# working.net
KiCad netlist of a schematic drawn in EAGLE
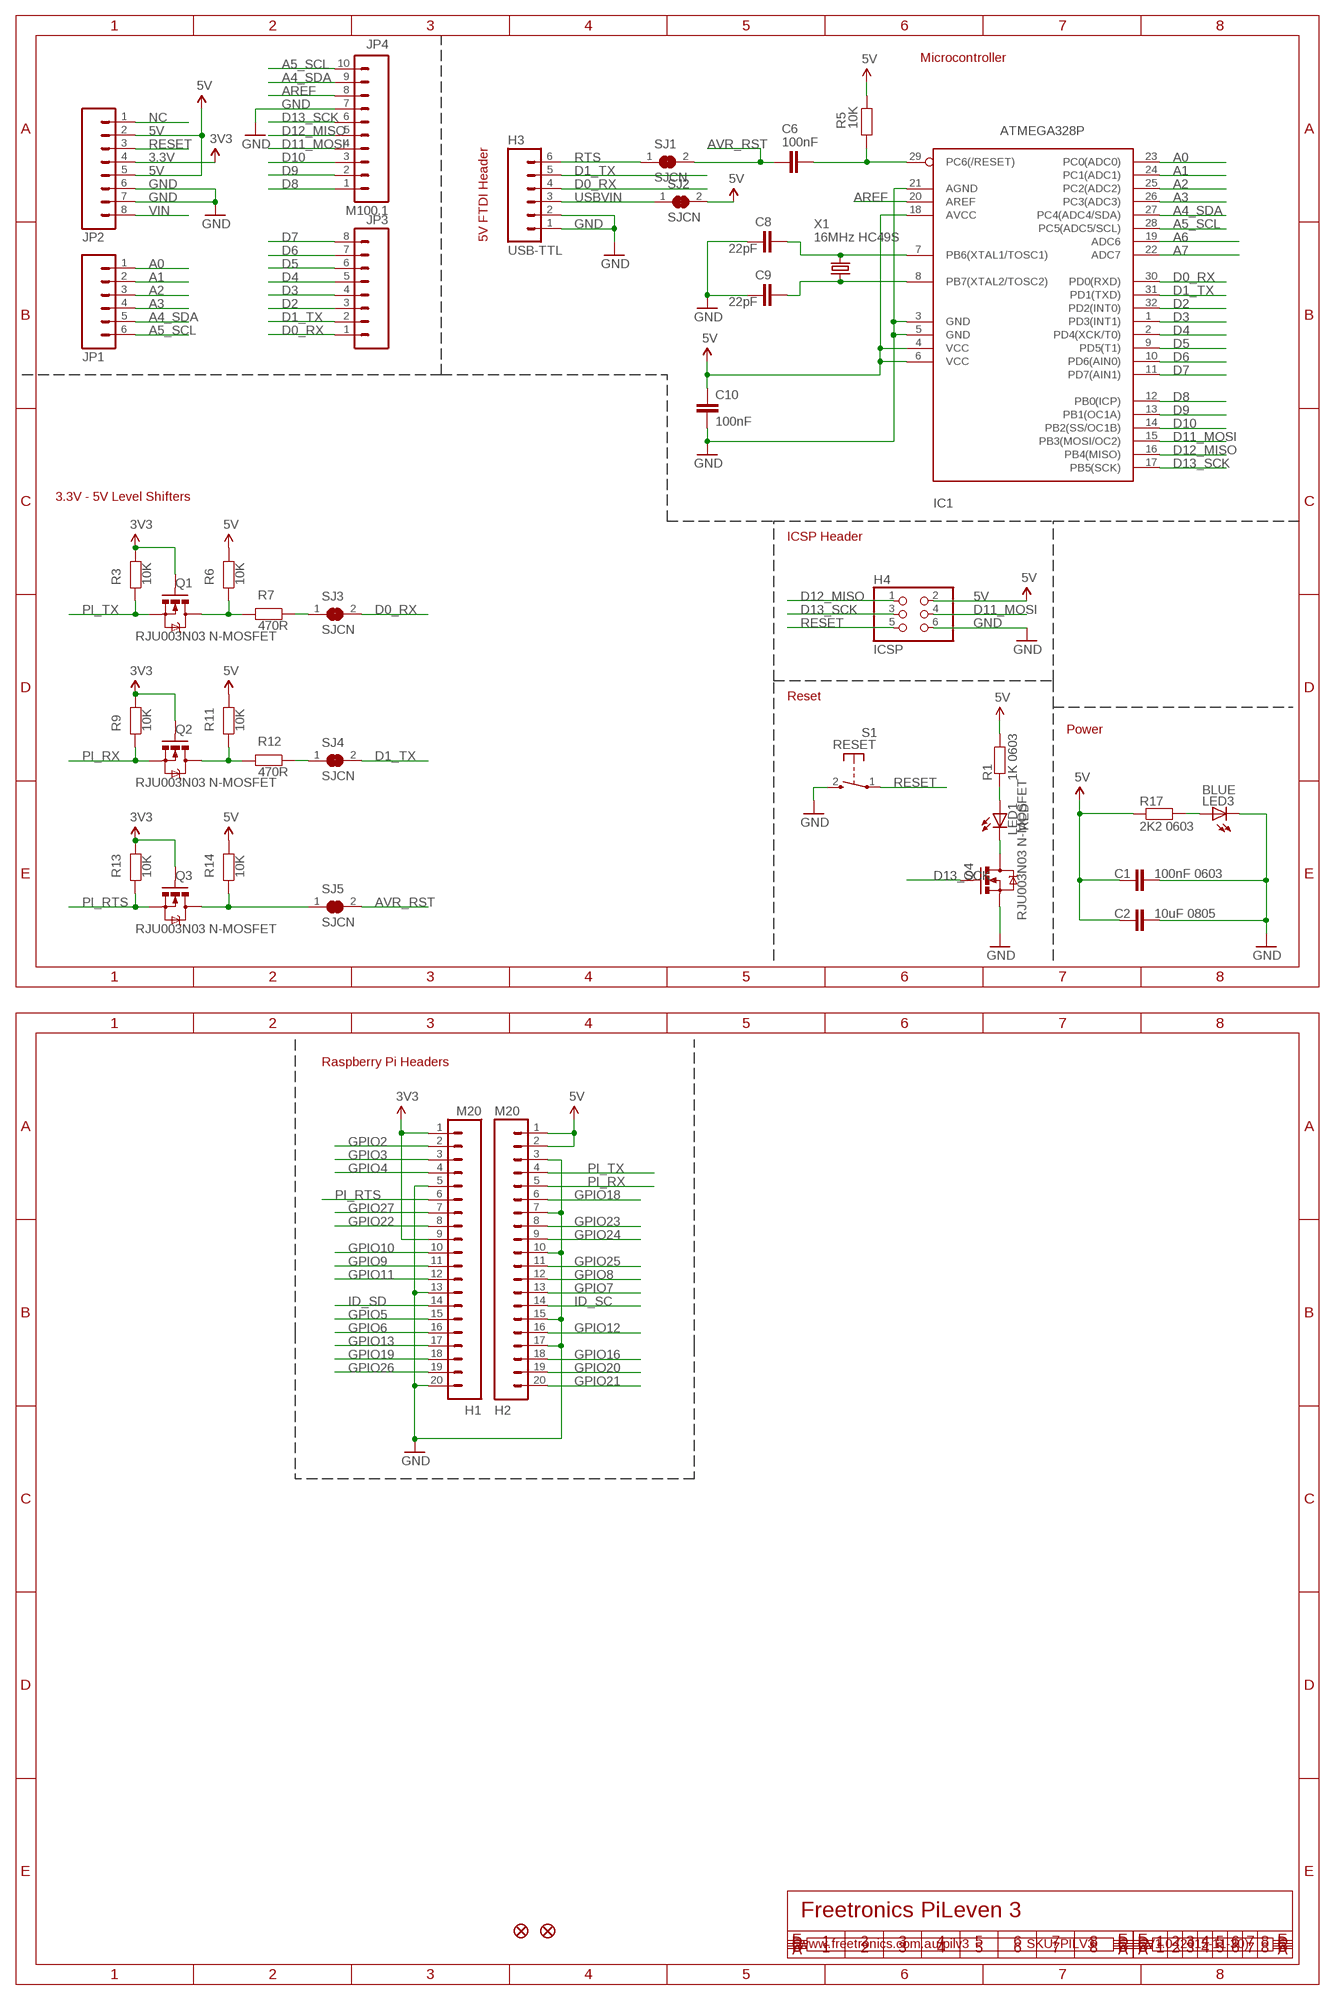
[diagram p0: schematic, sheet 1]

(export (version "E")
  (design (tool "Eeschema 10.0.6"))
  (components
    (comp (ref "C1")
      (value "100nF 0603")
      (footprint "eagle-import:0603")
      (libsource (lib "eagle-import") (part "CAP0603"))
    )
    (comp (ref "C2")
      (value "10uF 0805")
      (footprint "eagle-import:C0805")
      (libsource (lib "eagle-import") (part "C-EUC0805"))
    )
    (comp (ref "C6")
      (value "100nF")
      (footprint "eagle-import:0603")
      (libsource (lib "eagle-import") (part "freetronics-master-v1.1_CAP0603"))
    )
    (comp (ref "C8")
      (value "22pF")
      (footprint "eagle-import:0603")
      (libsource (lib "eagle-import") (part "freetronics-master-v1.1_CAP0603"))
    )
    (comp (ref "C9")
      (value "22pF")
      (footprint "eagle-import:0603")
      (libsource (lib "eagle-import") (part "freetronics-master-v1.1_CAP0603"))
    )
    (comp (ref "C10")
      (value "100nF")
      (footprint "eagle-import:0603")
      (libsource (lib "eagle-import") (part "freetronics-master-v1.1_CAP0603"))
    )
    (comp (ref "H1")
      (value "M20")
      (footprint "eagle-import:1X20")
      (libsource (lib "eagle-import") (part "M20"))
    )
    (comp (ref "H2")
      (value "M20")
      (footprint "eagle-import:1X20")
      (libsource (lib "eagle-import") (part "M20"))
    )
    (comp (ref "H3")
      (value "USB-TTL")
      (footprint "eagle-import:1X06")
      (libsource (lib "eagle-import") (part "M06SIP"))
    )
    (comp (ref "H4")
      (value "ICSP")
      (footprint "eagle-import:2X03")
      (libsource (lib "eagle-import") (part "PINHD-2X3"))
    )
    (comp (ref "IC1")
      (value "ATMEGA328P")
      (footprint "eagle-import:TQFP32-08")
      (libsource (lib "eagle-import") (part "AVR-MEGA8-AI"))
    )
    (comp (ref "JP1")
      (value "M06SIP")
      (footprint "eagle-import:1X06")
      (libsource (lib "eagle-import") (part "freetronics-original_M06SIP"))
    )
    (comp (ref "JP2")
      (value "M08")
      (footprint "eagle-import:1X08")
      (libsource (lib "eagle-import") (part "M08"))
    )
    (comp (ref "JP3")
      (value "M08")
      (footprint "eagle-import:1X08")
      (libsource (lib "eagle-import") (part "M08"))
    )
    (comp (ref "JP4")
      (value "M100.1")
      (footprint "eagle-import:1X10")
      (libsource (lib "eagle-import") (part "M100.1"))
    )
    (comp (ref "LED1")
      (value "RED")
      (footprint "eagle-import:LED-0603")
      (libsource (lib "eagle-import") (part "LED0603"))
    )
    (comp (ref "LED3")
      (value "BLUE")
      (footprint "eagle-import:LED-0603")
      (libsource (lib "eagle-import") (part "LED0603"))
    )
    (comp (ref "Q1")
      (value "RJU003N03 N-MOSFET")
      (footprint "eagle-import:SOT32-3")
      (libsource (lib "eagle-import") (part "MOSFET-NSOT-323"))
    )
    (comp (ref "Q2")
      (value "RJU003N03 N-MOSFET")
      (footprint "eagle-import:SOT32-3")
      (libsource (lib "eagle-import") (part "MOSFET-NSOT-323"))
    )
    (comp (ref "Q3")
      (value "RJU003N03 N-MOSFET")
      (footprint "eagle-import:SOT32-3")
      (libsource (lib "eagle-import") (part "MOSFET-NSOT-323"))
    )
    (comp (ref "Q4")
      (value "RJU003N03 N-MOSFET")
      (footprint "eagle-import:SOT32-3")
      (libsource (lib "eagle-import") (part "MOSFET-NSOT-323"))
    )
    (comp (ref "R1")
      (value "1K 0603")
      (footprint "eagle-import:0603")
      (libsource (lib "eagle-import") (part "RESISTOR0603"))
    )
    (comp (ref "R3")
      (value "10K")
      (footprint "eagle-import:0603")
      (libsource (lib "eagle-import") (part "freetronics-master-v1.1_RESISTOR0603"))
    )
    (comp (ref "R5")
      (value "10K")
      (footprint "eagle-import:0603")
      (libsource (lib "eagle-import") (part "freetronics-master-v1.1_RESISTOR0603"))
    )
    (comp (ref "R6")
      (value "10K")
      (footprint "eagle-import:0603")
      (libsource (lib "eagle-import") (part "freetronics-master-v1.1_RESISTOR0603"))
    )
    (comp (ref "R7")
      (value "470R")
      (footprint "eagle-import:0603")
      (libsource (lib "eagle-import") (part "freetronics-master-v1.1_RESISTOR0603"))
    )
    (comp (ref "R9")
      (value "10K")
      (footprint "eagle-import:0603")
      (libsource (lib "eagle-import") (part "freetronics-master-v1.1_RESISTOR0603"))
    )
    (comp (ref "R11")
      (value "10K")
      (footprint "eagle-import:0603")
      (libsource (lib "eagle-import") (part "freetronics-master-v1.1_RESISTOR0603"))
    )
    (comp (ref "R12")
      (value "470R")
      (footprint "eagle-import:0603")
      (libsource (lib "eagle-import") (part "freetronics-master-v1.1_RESISTOR0603"))
    )
    (comp (ref "R13")
      (value "10K")
      (footprint "eagle-import:0603")
      (libsource (lib "eagle-import") (part "freetronics-master-v1.1_RESISTOR0603"))
    )
    (comp (ref "R14")
      (value "10K")
      (footprint "eagle-import:0603")
      (libsource (lib "eagle-import") (part "freetronics-master-v1.1_RESISTOR0603"))
    )
    (comp (ref "R17")
      (value "2K2 0603")
      (footprint "eagle-import:0603")
      (libsource (lib "eagle-import") (part "RESISTOR0603"))
    )
    (comp (ref "S1")
      (value "RESET")
      (footprint "eagle-import:TACTILE_SWITCH_SMD_2PIN_TINY")
      (libsource (lib "eagle-import") (part "TAC_SWITCH_2PIN"))
    )
    (comp (ref "SJ1")
      (value "SJCN")
      (footprint "eagle-import:SJC")
      (libsource (lib "eagle-import") (part "SJCN"))
    )
    (comp (ref "SJ2")
      (value "SJCN")
      (footprint "eagle-import:SJC")
      (libsource (lib "eagle-import") (part "SJCN"))
    )
    (comp (ref "SJ3")
      (value "SJCN")
      (footprint "eagle-import:SJC")
      (libsource (lib "eagle-import") (part "SJCN"))
    )
    (comp (ref "SJ4")
      (value "SJCN")
      (footprint "eagle-import:SJC")
      (libsource (lib "eagle-import") (part "SJCN"))
    )
    (comp (ref "SJ5")
      (value "SJCN")
      (footprint "eagle-import:SJC")
      (libsource (lib "eagle-import") (part "SJCN"))
    )
    (comp (ref "U$4")
      (value "FIDUCIAL1X2.5")
      (footprint "eagle-import:FIDUCIAL-1X2.5")
      (libsource (lib "eagle-import") (part "FIDUCIAL1X2.5"))
    )
    (comp (ref "U$5")
      (value "FIDUCIAL1X2.5")
      (footprint "eagle-import:FIDUCIAL-1X2.5")
      (libsource (lib "eagle-import") (part "FIDUCIAL1X2.5"))
    )
    (comp (ref "X1")
      (value "16MHz HC49S")
      (footprint "eagle-import:HC49U-V")
      (libsource (lib "eagle-import") (part "CRYSTALHC49UV"))
    )
  )
  (nets
    (net (code "1") (name "/A0") (class "Default")
      (node (ref "IC1") (pin "23") (pinfunction "PC0(ADC0)_23") (pintype "bidirectional"))
      (node (ref "JP1") (pin "1") (pinfunction "1_1") (pintype "passive"))
    )
    (net (code "2") (name "/A1") (class "Default")
      (node (ref "IC1") (pin "24") (pinfunction "PC1(ADC1)_24") (pintype "bidirectional"))
      (node (ref "JP1") (pin "2") (pinfunction "2_2") (pintype "passive"))
    )
    (net (code "3") (name "/A2") (class "Default")
      (node (ref "IC1") (pin "25") (pinfunction "PC2(ADC2)_25") (pintype "bidirectional"))
      (node (ref "JP1") (pin "3") (pinfunction "3_3") (pintype "passive"))
    )
    (net (code "4") (name "/A3") (class "Default")
      (node (ref "IC1") (pin "26") (pinfunction "PC3(ADC3)_26") (pintype "bidirectional"))
      (node (ref "JP1") (pin "4") (pinfunction "4_4") (pintype "passive"))
    )
    (net (code "5") (name "/A4_SDA") (class "Default")
      (node (ref "IC1") (pin "27") (pinfunction "PC4(ADC4/SDA)_27") (pintype "bidirectional"))
      (node (ref "JP1") (pin "5") (pinfunction "5_5") (pintype "passive"))
      (node (ref "JP4") (pin "9") (pinfunction "9_9") (pintype "passive"))
    )
    (net (code "6") (name "/A5_SCL") (class "Default")
      (node (ref "IC1") (pin "28") (pinfunction "PC5(ADC5/SCL)_28") (pintype "bidirectional"))
      (node (ref "JP1") (pin "6") (pinfunction "6_6") (pintype "passive"))
      (node (ref "JP4") (pin "10") (pinfunction "10_10") (pintype "passive"))
    )
    (net (code "7") (name "/A6") (class "Default")
      (node (ref "IC1") (pin "19") (pinfunction "ADC6_19") (pintype "bidirectional"))
    )
    (net (code "8") (name "/A7") (class "Default")
      (node (ref "IC1") (pin "22") (pinfunction "ADC7_22") (pintype "bidirectional"))
    )
    (net (code "9") (name "/AREF") (class "Default")
      (node (ref "IC1") (pin "20") (pinfunction "AREF_20") (pintype "bidirectional"))
      (node (ref "JP4") (pin "8") (pinfunction "8_8") (pintype "passive"))
    )
    (net (code "10") (name "/AVR_RST") (class "Default")
      (node (ref "C6") (pin "1") (pinfunction "1_1") (pintype "passive"))
      (node (ref "SJ1") (pin "2") (pinfunction "2_2") (pintype "passive"))
      (node (ref "SJ5") (pin "2") (pinfunction "2_2") (pintype "passive"))
    )
    (net (code "11") (name "/D0_RX") (class "Default")
      (node (ref "H3") (pin "4") (pinfunction "4_4") (pintype "passive"))
      (node (ref "IC1") (pin "30") (pinfunction "PD0(RXD)_30") (pintype "bidirectional"))
      (node (ref "JP3") (pin "1") (pinfunction "1_1") (pintype "passive"))
      (node (ref "SJ3") (pin "2") (pinfunction "2_2") (pintype "passive"))
    )
    (net (code "12") (name "/D1_TX") (class "Default")
      (node (ref "H3") (pin "5") (pinfunction "5_5") (pintype "passive"))
      (node (ref "IC1") (pin "31") (pinfunction "PD1(TXD)_31") (pintype "bidirectional"))
      (node (ref "JP3") (pin "2") (pinfunction "2_2") (pintype "passive"))
      (node (ref "SJ4") (pin "2") (pinfunction "2_2") (pintype "passive"))
    )
    (net (code "13") (name "/D2") (class "Default")
      (node (ref "IC1") (pin "32") (pinfunction "PD2(INT0)_32") (pintype "bidirectional"))
      (node (ref "JP3") (pin "3") (pinfunction "3_3") (pintype "passive"))
    )
    (net (code "14") (name "/D3") (class "Default")
      (node (ref "IC1") (pin "1") (pinfunction "PD3(INT1)_1") (pintype "bidirectional"))
      (node (ref "JP3") (pin "4") (pinfunction "4_4") (pintype "passive"))
    )
    (net (code "15") (name "/D4") (class "Default")
      (node (ref "IC1") (pin "2") (pinfunction "PD4(XCK/T0)_2") (pintype "bidirectional"))
      (node (ref "JP3") (pin "5") (pinfunction "5_5") (pintype "passive"))
    )
    (net (code "16") (name "/D5") (class "Default")
      (node (ref "IC1") (pin "9") (pinfunction "PD5(T1)_9") (pintype "bidirectional"))
      (node (ref "JP3") (pin "6") (pinfunction "6_6") (pintype "passive"))
    )
    (net (code "17") (name "/D6") (class "Default")
      (node (ref "IC1") (pin "10") (pinfunction "PD6(AIN0)_10") (pintype "bidirectional"))
      (node (ref "JP3") (pin "7") (pinfunction "7_7") (pintype "passive"))
    )
    (net (code "18") (name "/D7") (class "Default")
      (node (ref "IC1") (pin "11") (pinfunction "PD7(AIN1)_11") (pintype "bidirectional"))
      (node (ref "JP3") (pin "8") (pinfunction "8_8") (pintype "passive"))
    )
    (net (code "19") (name "/D8") (class "Default")
      (node (ref "IC1") (pin "12") (pinfunction "PB0(ICP)_12") (pintype "bidirectional"))
      (node (ref "JP4") (pin "1") (pinfunction "1_1") (pintype "passive"))
    )
    (net (code "20") (name "/D9") (class "Default")
      (node (ref "IC1") (pin "13") (pinfunction "PB1(OC1A)_13") (pintype "bidirectional"))
      (node (ref "JP4") (pin "2") (pinfunction "2_2") (pintype "passive"))
    )
    (net (code "21") (name "/D10") (class "Default")
      (node (ref "IC1") (pin "14") (pinfunction "PB2(SS/OC1B)_14") (pintype "bidirectional"))
      (node (ref "JP4") (pin "3") (pinfunction "3_3") (pintype "passive"))
    )
    (net (code "22") (name "/D11_MOSI") (class "Default")
      (node (ref "H4") (pin "4") (pinfunction "4_4") (pintype "passive"))
      (node (ref "IC1") (pin "15") (pinfunction "PB3(MOSI/OC2)_15") (pintype "bidirectional"))
      (node (ref "JP4") (pin "4") (pinfunction "4_4") (pintype "passive"))
    )
    (net (code "23") (name "/D12_MISO") (class "Default")
      (node (ref "H4") (pin "1") (pinfunction "1_1") (pintype "passive"))
      (node (ref "IC1") (pin "16") (pinfunction "PB4(MISO)_16") (pintype "bidirectional"))
      (node (ref "JP4") (pin "5") (pinfunction "5_5") (pintype "passive"))
    )
    (net (code "24") (name "/D13_SCK") (class "Default")
      (node (ref "H4") (pin "3") (pinfunction "3_3") (pintype "passive"))
      (node (ref "IC1") (pin "17") (pinfunction "PB5(SCK)_17") (pintype "bidirectional"))
      (node (ref "JP4") (pin "6") (pinfunction "6_6") (pintype "passive"))
      (node (ref "Q4") (pin "1") (pinfunction "G_1") (pintype "passive"))
    )
    (net (code "25") (name "/GPIO2") (class "Default")
      (node (ref "H1") (pin "2") (pinfunction "2_2") (pintype "passive"))
    )
    (net (code "26") (name "/GPIO3") (class "Default")
      (node (ref "H1") (pin "3") (pinfunction "3_3") (pintype "passive"))
    )
    (net (code "27") (name "/GPIO4") (class "Default")
      (node (ref "H1") (pin "4") (pinfunction "4_4") (pintype "passive"))
    )
    (net (code "28") (name "/GPIO5") (class "Default")
      (node (ref "H1") (pin "15") (pinfunction "15_15") (pintype "passive"))
    )
    (net (code "29") (name "/GPIO6") (class "Default")
      (node (ref "H1") (pin "16") (pinfunction "16_16") (pintype "passive"))
    )
    (net (code "30") (name "/GPIO7") (class "Default")
      (node (ref "H2") (pin "13") (pinfunction "13_13") (pintype "passive"))
    )
    (net (code "31") (name "/GPIO8") (class "Default")
      (node (ref "H2") (pin "12") (pinfunction "12_12") (pintype "passive"))
    )
    (net (code "32") (name "/GPIO9") (class "Default")
      (node (ref "H1") (pin "11") (pinfunction "11_11") (pintype "passive"))
    )
    (net (code "33") (name "/GPIO10") (class "Default")
      (node (ref "H1") (pin "10") (pinfunction "10_10") (pintype "passive"))
    )
    (net (code "34") (name "/GPIO11") (class "Default")
      (node (ref "H1") (pin "12") (pinfunction "12_12") (pintype "passive"))
    )
    (net (code "35") (name "/GPIO12") (class "Default")
      (node (ref "H2") (pin "16") (pinfunction "16_16") (pintype "passive"))
    )
    (net (code "36") (name "/GPIO13") (class "Default")
      (node (ref "H1") (pin "17") (pinfunction "17_17") (pintype "passive"))
    )
    (net (code "37") (name "/GPIO16") (class "Default")
      (node (ref "H2") (pin "18") (pinfunction "18_18") (pintype "passive"))
    )
    (net (code "38") (name "/GPIO18") (class "Default")
      (node (ref "H2") (pin "6") (pinfunction "6_6") (pintype "passive"))
    )
    (net (code "39") (name "/GPIO19") (class "Default")
      (node (ref "H1") (pin "18") (pinfunction "18_18") (pintype "passive"))
    )
    (net (code "40") (name "/GPIO20") (class "Default")
      (node (ref "H2") (pin "19") (pinfunction "19_19") (pintype "passive"))
    )
    (net (code "41") (name "/GPIO21") (class "Default")
      (node (ref "H2") (pin "20") (pinfunction "20_20") (pintype "passive"))
    )
    (net (code "42") (name "/GPIO22") (class "Default")
      (node (ref "H1") (pin "8") (pinfunction "8_8") (pintype "passive"))
    )
    (net (code "43") (name "/GPIO23") (class "Default")
      (node (ref "H2") (pin "8") (pinfunction "8_8") (pintype "passive"))
    )
    (net (code "44") (name "/GPIO24") (class "Default")
      (node (ref "H2") (pin "9") (pinfunction "9_9") (pintype "passive"))
    )
    (net (code "45") (name "/GPIO25") (class "Default")
      (node (ref "H2") (pin "11") (pinfunction "11_11") (pintype "passive"))
    )
    (net (code "46") (name "/GPIO26") (class "Default")
      (node (ref "H1") (pin "19") (pinfunction "19_19") (pintype "passive"))
    )
    (net (code "47") (name "/GPIO27") (class "Default")
      (node (ref "H1") (pin "7") (pinfunction "7_7") (pintype "passive"))
    )
    (net (code "48") (name "/ID_SC") (class "Default")
      (node (ref "H2") (pin "14") (pinfunction "14_14") (pintype "passive"))
    )
    (net (code "49") (name "/ID_SD") (class "Default")
      (node (ref "H1") (pin "14") (pinfunction "14_14") (pintype "passive"))
    )
    (net (code "50") (name "/NC") (class "Default")
      (node (ref "JP2") (pin "1") (pinfunction "1_1") (pintype "passive"))
    )
    (net (code "51") (name "/PI_RTS") (class "Default")
      (node (ref "H1") (pin "6") (pinfunction "6_6") (pintype "passive"))
      (node (ref "Q3") (pin "2") (pinfunction "S_2") (pintype "passive"))
      (node (ref "R13") (pin "2") (pinfunction "2_2") (pintype "passive"))
    )
    (net (code "52") (name "/PI_RX") (class "Default")
      (node (ref "H2") (pin "5") (pinfunction "5_5") (pintype "passive"))
      (node (ref "Q2") (pin "2") (pinfunction "S_2") (pintype "passive"))
      (node (ref "R9") (pin "2") (pinfunction "2_2") (pintype "passive"))
    )
    (net (code "53") (name "/PI_TX") (class "Default")
      (node (ref "H2") (pin "4") (pinfunction "4_4") (pintype "passive"))
      (node (ref "Q1") (pin "2") (pinfunction "S_2") (pintype "passive"))
      (node (ref "R3") (pin "2") (pinfunction "2_2") (pintype "passive"))
    )
    (net (code "54") (name "/RESET") (class "Default")
      (node (ref "C6") (pin "2") (pinfunction "2_2") (pintype "passive"))
      (node (ref "H4") (pin "5") (pinfunction "5_5") (pintype "passive"))
      (node (ref "IC1") (pin "29") (pinfunction "PC6(/RESET)_29") (pintype "bidirectional"))
      (node (ref "JP2") (pin "3") (pinfunction "3_3") (pintype "passive"))
      (node (ref "R5") (pin "1") (pinfunction "1_1") (pintype "passive"))
      (node (ref "S1") (pin "1") (pinfunction "P_1") (pintype "passive"))
    )
    (net (code "55") (name "/RTS") (class "Default")
      (node (ref "H3") (pin "6") (pinfunction "6_6") (pintype "passive"))
      (node (ref "SJ1") (pin "1") (pinfunction "1_1") (pintype "passive"))
    )
    (net (code "56") (name "/USBVIN") (class "Default")
      (node (ref "H3") (pin "3") (pinfunction "3_3") (pintype "passive"))
      (node (ref "SJ2") (pin "1") (pinfunction "1_1") (pintype "passive"))
    )
    (net (code "57") (name "/VIN") (class "Default")
      (node (ref "JP2") (pin "8") (pinfunction "8_8") (pintype "passive"))
    )
    (net (code "58") (name "3V3") (class "Default")
      (node (ref "H1") (pin "1") (pinfunction "1_1") (pintype "passive"))
      (node (ref "H1") (pin "9") (pinfunction "9_9") (pintype "passive"))
      (node (ref "JP2") (pin "4") (pinfunction "4_4") (pintype "passive"))
      (node (ref "Q1") (pin "1") (pinfunction "G_1") (pintype "passive"))
      (node (ref "Q2") (pin "1") (pinfunction "G_1") (pintype "passive"))
      (node (ref "Q3") (pin "1") (pinfunction "G_1") (pintype "passive"))
      (node (ref "R13") (pin "1") (pinfunction "1_1") (pintype "passive"))
      (node (ref "R3") (pin "1") (pinfunction "1_1") (pintype "passive"))
      (node (ref "R9") (pin "1") (pinfunction "1_1") (pintype "passive"))
    )
    (net (code "59") (name "5V") (class "Default")
      (node (ref "C1") (pin "1") (pinfunction "1_1") (pintype "passive"))
      (node (ref "C10") (pin "1") (pinfunction "1_1") (pintype "passive"))
      (node (ref "C2") (pin "2") (pinfunction "2_2") (pintype "passive"))
      (node (ref "H2") (pin "1") (pinfunction "1_1") (pintype "passive"))
      (node (ref "H2") (pin "2") (pinfunction "2_2") (pintype "passive"))
      (node (ref "H4") (pin "2") (pinfunction "2_2") (pintype "passive"))
      (node (ref "IC1") (pin "18") (pinfunction "AVCC_18") (pintype "bidirectional"))
      (node (ref "IC1") (pin "4") (pinfunction "VCC_4") (pintype "bidirectional"))
      (node (ref "IC1") (pin "6") (pinfunction "VCC_6") (pintype "bidirectional"))
      (node (ref "JP2") (pin "2") (pinfunction "2_2") (pintype "passive"))
      (node (ref "JP2") (pin "5") (pinfunction "5_5") (pintype "passive"))
      (node (ref "R1") (pin "2") (pinfunction "2_2") (pintype "passive"))
      (node (ref "R11") (pin "1") (pinfunction "1_1") (pintype "passive"))
      (node (ref "R14") (pin "1") (pinfunction "1_1") (pintype "passive"))
      (node (ref "R17") (pin "1") (pinfunction "1_1") (pintype "passive"))
      (node (ref "R5") (pin "2") (pinfunction "2_2") (pintype "passive"))
      (node (ref "R6") (pin "1") (pinfunction "1_1") (pintype "passive"))
      (node (ref "SJ2") (pin "2") (pinfunction "2_2") (pintype "passive"))
    )
    (net (code "60") (name "GND") (class "Default")
      (node (ref "C1") (pin "2") (pinfunction "2_2") (pintype "passive"))
      (node (ref "C10") (pin "2") (pinfunction "2_2") (pintype "passive"))
      (node (ref "C2") (pin "1") (pinfunction "1_1") (pintype "passive"))
      (node (ref "C8") (pin "1") (pinfunction "1_1") (pintype "passive"))
      (node (ref "C9") (pin "1") (pinfunction "1_1") (pintype "passive"))
      (node (ref "H1") (pin "13") (pinfunction "13_13") (pintype "passive"))
      (node (ref "H1") (pin "20") (pinfunction "20_20") (pintype "passive"))
      (node (ref "H1") (pin "5") (pinfunction "5_5") (pintype "passive"))
      (node (ref "H2") (pin "10") (pinfunction "10_10") (pintype "passive"))
      (node (ref "H2") (pin "15") (pinfunction "15_15") (pintype "passive"))
      (node (ref "H2") (pin "17") (pinfunction "17_17") (pintype "passive"))
      (node (ref "H2") (pin "3") (pinfunction "3_3") (pintype "passive"))
      (node (ref "H2") (pin "7") (pinfunction "7_7") (pintype "passive"))
      (node (ref "H3") (pin "1") (pinfunction "1_1") (pintype "passive"))
      (node (ref "H3") (pin "2") (pinfunction "2_2") (pintype "passive"))
      (node (ref "H4") (pin "6") (pinfunction "6_6") (pintype "passive"))
      (node (ref "IC1") (pin "21") (pinfunction "AGND_21") (pintype "bidirectional"))
      (node (ref "IC1") (pin "3") (pinfunction "GND_3") (pintype "bidirectional"))
      (node (ref "IC1") (pin "5") (pinfunction "GND_5") (pintype "bidirectional"))
      (node (ref "JP2") (pin "6") (pinfunction "6_6") (pintype "passive"))
      (node (ref "JP2") (pin "7") (pinfunction "7_7") (pintype "passive"))
      (node (ref "JP4") (pin "7") (pinfunction "7_7") (pintype "passive"))
      (node (ref "LED3") (pin "C") (pinfunction "C_C") (pintype "passive"))
      (node (ref "Q4") (pin "2") (pinfunction "S_2") (pintype "passive"))
      (node (ref "S1") (pin "2") (pinfunction "S_2") (pintype "passive"))
    )
    (net (code "61") (name "Net-(IC1-PB6(XTAL1{slash}TOSC1))") (class "Default")
      (node (ref "C8") (pin "2") (pinfunction "2_2") (pintype "passive"))
      (node (ref "IC1") (pin "7") (pinfunction "PB6(XTAL1/TOSC1)_7") (pintype "bidirectional"))
      (node (ref "X1") (pin "2") (pinfunction "2_2") (pintype "passive"))
    )
    (net (code "62") (name "Net-(IC1-PB7(XTAL2{slash}TOSC2))") (class "Default")
      (node (ref "C9") (pin "2") (pinfunction "2_2") (pintype "passive"))
      (node (ref "IC1") (pin "8") (pinfunction "PB7(XTAL2/TOSC2)_8") (pintype "bidirectional"))
      (node (ref "X1") (pin "1") (pinfunction "1_1") (pintype "passive"))
    )
    (net (code "63") (name "Net-(LED1-PadA)") (class "Default")
      (node (ref "LED1") (pin "A") (pinfunction "A_A") (pintype "passive"))
      (node (ref "R1") (pin "1") (pinfunction "1_1") (pintype "passive"))
    )
    (net (code "64") (name "Net-(LED3-PadA)") (class "Default")
      (node (ref "LED3") (pin "A") (pinfunction "A_A") (pintype "passive"))
      (node (ref "R17") (pin "2") (pinfunction "2_2") (pintype "passive"))
    )
    (net (code "65") (name "Net-(Q1-D)") (class "Default")
      (node (ref "Q1") (pin "3") (pinfunction "D_3") (pintype "passive"))
      (node (ref "R6") (pin "2") (pinfunction "2_2") (pintype "passive"))
      (node (ref "R7") (pin "2") (pinfunction "2_2") (pintype "passive"))
    )
    (net (code "66") (name "Net-(Q2-D)") (class "Default")
      (node (ref "Q2") (pin "3") (pinfunction "D_3") (pintype "passive"))
      (node (ref "R11") (pin "2") (pinfunction "2_2") (pintype "passive"))
      (node (ref "R12") (pin "2") (pinfunction "2_2") (pintype "passive"))
    )
    (net (code "67") (name "Net-(Q3-D)") (class "Default")
      (node (ref "Q3") (pin "3") (pinfunction "D_3") (pintype "passive"))
      (node (ref "R14") (pin "2") (pinfunction "2_2") (pintype "passive"))
      (node (ref "SJ5") (pin "1") (pinfunction "1_1") (pintype "passive"))
    )
    (net (code "68") (name "Net-(Q4-D)") (class "Default")
      (node (ref "LED1") (pin "C") (pinfunction "C_C") (pintype "passive"))
      (node (ref "Q4") (pin "3") (pinfunction "D_3") (pintype "passive"))
    )
    (net (code "69") (name "Net-(R7-Pad1)") (class "Default")
      (node (ref "R7") (pin "1") (pinfunction "1_1") (pintype "passive"))
      (node (ref "SJ3") (pin "1") (pinfunction "1_1") (pintype "passive"))
    )
    (net (code "70") (name "Net-(R12-Pad1)") (class "Default")
      (node (ref "R12") (pin "1") (pinfunction "1_1") (pintype "passive"))
      (node (ref "SJ4") (pin "1") (pinfunction "1_1") (pintype "passive"))
    )
  )
)
